# Sheet1.net
KiCad netlist of a schematic drawn in Altium Designer
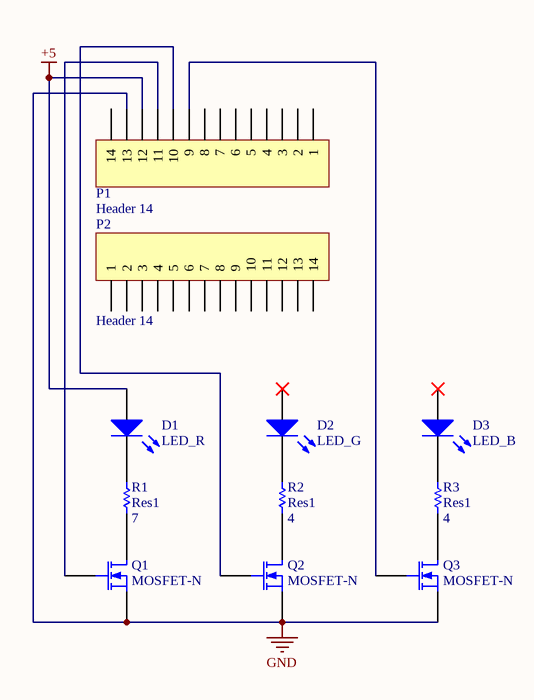
[diagram p0: Sheet1.SchDoc]

(export (version "E")
  (design (tool "Eeschema 10.0.6"))
  (components
    (comp (ref "D1")
      (value "LED_R")
      (footprint "LED-0")
      (description "Typical INFRARED GaAs LED")
      (fields (field (name "PUBLISHER") "Altium Limited"))
      (libsource (lib "Miscellaneous Devices") (part "LED0"))
    )
    (comp (ref "D2")
      (value "LED_G")
      (footprint "LED-0")
      (description "Typical INFRARED GaAs LED")
      (fields (field (name "PUBLISHER") "Altium Limited"))
      (libsource (lib "Miscellaneous Devices") (part "LED0"))
    )
    (comp (ref "D3")
      (value "LED_B")
      (footprint "LED-0")
      (description "Typical INFRARED GaAs LED")
      (fields (field (name "PUBLISHER") "Altium Limited"))
      (libsource (lib "Miscellaneous Devices") (part "LED0"))
    )
    (comp (ref "P1")
      (value "Header 14")
      (footprint "HDR1X14")
      (description "Header, 14-Pin")
      (fields (field (name "PUBLISHER") "Altium Limited"))
      (libsource (lib "Miscellaneous Connectors") (part "Header 14"))
    )
    (comp (ref "P2")
      (value "Header 14")
      (footprint "HDR1X14")
      (description "Header, 14-Pin")
      (fields (field (name "PUBLISHER") "Altium Limited"))
      (libsource (lib "") (part "Header 14_1"))
    )
    (comp (ref "Q1")
      (value "MOSFET-N")
      (footprint "E3")
      (description "N-Channel MOSFET")
      (fields (field (name "PUBLISHER") "Altium Limited"))
      (libsource (lib "Miscellaneous Devices") (part "MOSFET-N"))
    )
    (comp (ref "Q2")
      (value "MOSFET-N")
      (footprint "E3")
      (description "N-Channel MOSFET")
      (fields (field (name "PUBLISHER") "Altium Limited"))
      (libsource (lib "Miscellaneous Devices") (part "MOSFET-N"))
    )
    (comp (ref "Q3")
      (value "MOSFET-N")
      (footprint "E3")
      (description "N-Channel MOSFET")
      (fields (field (name "PUBLISHER") "Altium Limited"))
      (libsource (lib "Miscellaneous Devices") (part "MOSFET-N"))
    )
    (comp (ref "R1")
      (value "Res1")
      (footprint "AXIAL-0.3")
      (description "Resistor")
      (fields (field (name "ALTIUM_VALUE") "7") (field (name "PUBLISHER") "Altium Limited"))
      (libsource (lib "Miscellaneous Devices") (part "Res1"))
    )
    (comp (ref "R2")
      (value "Res1")
      (footprint "AXIAL-0.3")
      (description "Resistor")
      (fields (field (name "ALTIUM_VALUE") "4") (field (name "PUBLISHER") "Altium Limited"))
      (libsource (lib "Miscellaneous Devices") (part "Res1"))
    )
    (comp (ref "R3")
      (value "Res1")
      (footprint "AXIAL-0.3")
      (description "Resistor")
      (fields (field (name "ALTIUM_VALUE") "4") (field (name "PUBLISHER") "Altium Limited"))
      (libsource (lib "Miscellaneous Devices") (part "Res1"))
    )
  )
  (nets
    (net (code "1") (name "+5") (class "Default")
      (node (ref "D1") (pin "1") (pinfunction "A_1") (pintype "passive"))
      (node (ref "P1") (pin "12") (pinfunction "12_12") (pintype "passive"))
    )
    (net (code "2") (name "GND") (class "Default")
      (node (ref "P1") (pin "13") (pinfunction "13_13") (pintype "passive"))
      (node (ref "Q1") (pin "3") (pinfunction "S_3") (pintype "passive"))
      (node (ref "Q2") (pin "3") (pinfunction "S_3") (pintype "passive"))
      (node (ref "Q3") (pin "3") (pinfunction "S_3") (pintype "passive"))
    )
    (net (code "3") (name "Net-(D1-K)") (class "Default")
      (node (ref "D1") (pin "2") (pinfunction "K_2") (pintype "passive"))
      (node (ref "R1") (pin "2") (pinfunction "2_2") (pintype "passive"))
    )
    (net (code "4") (name "Net-(D2-K)") (class "Default")
      (node (ref "D2") (pin "2") (pinfunction "K_2") (pintype "passive"))
      (node (ref "R2") (pin "2") (pinfunction "2_2") (pintype "passive"))
    )
    (net (code "5") (name "Net-(D3-K)") (class "Default")
      (node (ref "D3") (pin "2") (pinfunction "K_2") (pintype "passive"))
      (node (ref "R3") (pin "2") (pinfunction "2_2") (pintype "passive"))
    )
    (net (code "6") (name "Net-(Q1-D)") (class "Default")
      (node (ref "Q1") (pin "1") (pinfunction "D_1") (pintype "passive"))
      (node (ref "R1") (pin "1") (pinfunction "1_1") (pintype "passive"))
    )
    (net (code "7") (name "Net-(Q1-G)") (class "Default")
      (node (ref "P1") (pin "11") (pinfunction "11_11") (pintype "passive"))
      (node (ref "Q1") (pin "2") (pinfunction "G_2") (pintype "passive"))
    )
    (net (code "8") (name "Net-(Q2-D)") (class "Default")
      (node (ref "Q2") (pin "1") (pinfunction "D_1") (pintype "passive"))
      (node (ref "R2") (pin "1") (pinfunction "1_1") (pintype "passive"))
    )
    (net (code "9") (name "Net-(Q2-G)") (class "Default")
      (node (ref "P1") (pin "10") (pinfunction "10_10") (pintype "passive"))
      (node (ref "Q2") (pin "2") (pinfunction "G_2") (pintype "passive"))
    )
    (net (code "10") (name "Net-(Q3-D)") (class "Default")
      (node (ref "Q3") (pin "1") (pinfunction "D_1") (pintype "passive"))
      (node (ref "R3") (pin "1") (pinfunction "1_1") (pintype "passive"))
    )
    (net (code "11") (name "Net-(Q3-G)") (class "Default")
      (node (ref "P1") (pin "9") (pinfunction "9_9") (pintype "passive"))
      (node (ref "Q3") (pin "2") (pinfunction "G_2") (pintype "passive"))
    )
    (net (code "12") (name "unconnected-(D2-A-Pad1)") (class "Default")
      (node (ref "D2") (pin "1") (pinfunction "A_1") (pintype "passive+no_connect"))
    )
    (net (code "13") (name "unconnected-(D3-A-Pad1)") (class "Default")
      (node (ref "D3") (pin "1") (pinfunction "A_1") (pintype "passive+no_connect"))
    )
    (net (code "14") (name "unconnected-(P1-Pad1)") (class "Default")
      (node (ref "P1") (pin "1") (pinfunction "1_1") (pintype "passive"))
    )
    (net (code "15") (name "unconnected-(P1-Pad2)") (class "Default")
      (node (ref "P1") (pin "2") (pinfunction "2_2") (pintype "passive"))
    )
    (net (code "16") (name "unconnected-(P1-Pad3)") (class "Default")
      (node (ref "P1") (pin "3") (pinfunction "3_3") (pintype "passive"))
    )
    (net (code "17") (name "unconnected-(P1-Pad4)") (class "Default")
      (node (ref "P1") (pin "4") (pinfunction "4_4") (pintype "passive"))
    )
    (net (code "18") (name "unconnected-(P1-Pad5)") (class "Default")
      (node (ref "P1") (pin "5") (pinfunction "5_5") (pintype "passive"))
    )
    (net (code "19") (name "unconnected-(P1-Pad6)") (class "Default")
      (node (ref "P1") (pin "6") (pinfunction "6_6") (pintype "passive"))
    )
    (net (code "20") (name "unconnected-(P1-Pad7)") (class "Default")
      (node (ref "P1") (pin "7") (pinfunction "7_7") (pintype "passive"))
    )
    (net (code "21") (name "unconnected-(P1-Pad8)") (class "Default")
      (node (ref "P1") (pin "8") (pinfunction "8_8") (pintype "passive"))
    )
    (net (code "22") (name "unconnected-(P1-Pad14)") (class "Default")
      (node (ref "P1") (pin "14") (pinfunction "14_14") (pintype "passive"))
    )
    (net (code "23") (name "unconnected-(P2-Pad1)") (class "Default")
      (node (ref "P2") (pin "1") (pinfunction "1_1") (pintype "passive"))
    )
    (net (code "24") (name "unconnected-(P2-Pad2)") (class "Default")
      (node (ref "P2") (pin "2") (pinfunction "2_2") (pintype "passive"))
    )
    (net (code "25") (name "unconnected-(P2-Pad3)") (class "Default")
      (node (ref "P2") (pin "3") (pinfunction "3_3") (pintype "passive"))
    )
    (net (code "26") (name "unconnected-(P2-Pad4)") (class "Default")
      (node (ref "P2") (pin "4") (pinfunction "4_4") (pintype "passive"))
    )
    (net (code "27") (name "unconnected-(P2-Pad5)") (class "Default")
      (node (ref "P2") (pin "5") (pinfunction "5_5") (pintype "passive"))
    )
    (net (code "28") (name "unconnected-(P2-Pad6)") (class "Default")
      (node (ref "P2") (pin "6") (pinfunction "6_6") (pintype "passive"))
    )
    (net (code "29") (name "unconnected-(P2-Pad7)") (class "Default")
      (node (ref "P2") (pin "7") (pinfunction "7_7") (pintype "passive"))
    )
    (net (code "30") (name "unconnected-(P2-Pad8)") (class "Default")
      (node (ref "P2") (pin "8") (pinfunction "8_8") (pintype "passive"))
    )
    (net (code "31") (name "unconnected-(P2-Pad9)") (class "Default")
      (node (ref "P2") (pin "9") (pinfunction "9_9") (pintype "passive"))
    )
    (net (code "32") (name "unconnected-(P2-Pad10)") (class "Default")
      (node (ref "P2") (pin "10") (pinfunction "10_10") (pintype "passive"))
    )
    (net (code "33") (name "unconnected-(P2-Pad11)") (class "Default")
      (node (ref "P2") (pin "11") (pinfunction "11_11") (pintype "passive"))
    )
    (net (code "34") (name "unconnected-(P2-Pad12)") (class "Default")
      (node (ref "P2") (pin "12") (pinfunction "12_12") (pintype "passive"))
    )
    (net (code "35") (name "unconnected-(P2-Pad13)") (class "Default")
      (node (ref "P2") (pin "13") (pinfunction "13_13") (pintype "passive"))
    )
    (net (code "36") (name "unconnected-(P2-Pad14)") (class "Default")
      (node (ref "P2") (pin "14") (pinfunction "14_14") (pintype "passive"))
    )
  )
)
